# eggbothat2.net
KiCad netlist of a schematic drawn in EAGLE
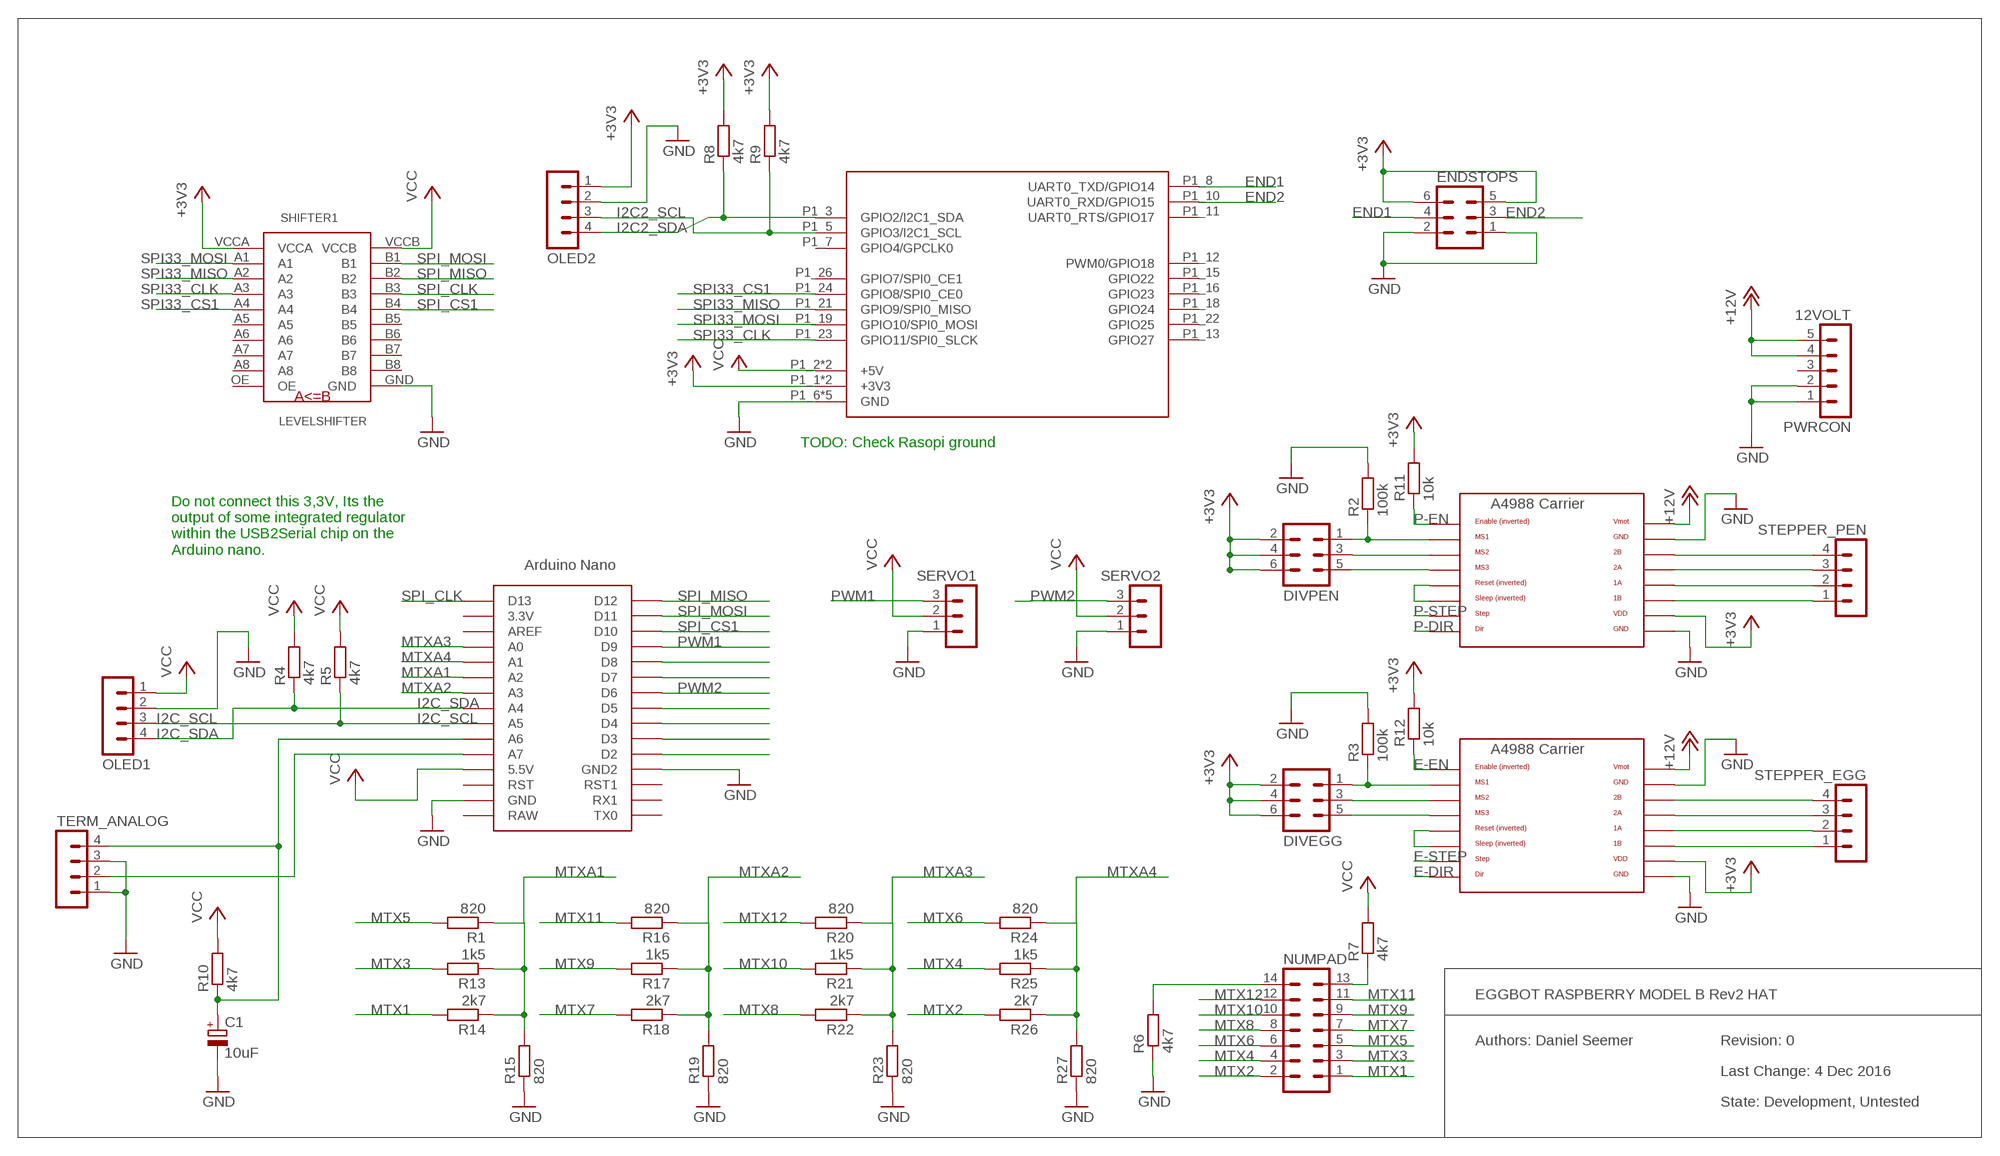
[diagram p0: schematic, sheet 1]

(export (version "E")
  (design (tool "Eeschema 10.0.6"))
  (components
    (comp (ref "12VOLT")
      (value "PWRCON")
      (footprint "eagle-import:MA05-1")
      (libsource (lib "eagle-import") (part "MA05-1"))
    )
    (comp (ref "C1")
      (value "10uF")
      (footprint "eagle-import:E2,5-5")
      (libsource (lib "eagle-import") (part "CPOL-EUE2.5-5"))
    )
    (comp (ref "DIVEGG")
      (value "MA03-2")
      (footprint "eagle-import:MA03-2")
      (libsource (lib "eagle-import") (part "MA03-2"))
    )
    (comp (ref "DIVPEN")
      (value "MA03-2")
      (footprint "eagle-import:MA03-2")
      (libsource (lib "eagle-import") (part "MA03-2"))
    )
    (comp (ref "ENDSTOPS")
      (value "MA03-2")
      (footprint "eagle-import:MA03-2")
      (libsource (lib "eagle-import") (part "MA03-2"))
    )
    (comp (ref "NUMPAD")
      (value "MA07-2")
      (footprint "eagle-import:MA07-2")
      (libsource (lib "eagle-import") (part "MA07-2"))
    )
    (comp (ref "OLED1")
      (value "MA04-1")
      (footprint "eagle-import:MA04-1")
      (libsource (lib "eagle-import") (part "MA04-1"))
    )
    (comp (ref "OLED2")
      (value "MA04-1")
      (footprint "eagle-import:MA04-1")
      (libsource (lib "eagle-import") (part "MA04-1"))
    )
    (comp (ref "R1")
      (value "820")
      (footprint "eagle-import:R1206")
      (libsource (lib "eagle-import") (part "R-EU_R1206"))
    )
    (comp (ref "R2")
      (value "100k")
      (footprint "eagle-import:R1206")
      (libsource (lib "eagle-import") (part "R-EU_R1206"))
    )
    (comp (ref "R3")
      (value "100k")
      (footprint "eagle-import:R1206")
      (libsource (lib "eagle-import") (part "R-EU_R1206"))
    )
    (comp (ref "R4")
      (value "4k7")
      (footprint "eagle-import:R1206")
      (libsource (lib "eagle-import") (part "R-EU_R1206"))
    )
    (comp (ref "R5")
      (value "4k7")
      (footprint "eagle-import:R1206")
      (libsource (lib "eagle-import") (part "R-EU_R1206"))
    )
    (comp (ref "R6")
      (value "4k7")
      (footprint "eagle-import:R1206")
      (libsource (lib "eagle-import") (part "R-EU_R1206"))
    )
    (comp (ref "R7")
      (value "4k7")
      (footprint "eagle-import:R1206")
      (libsource (lib "eagle-import") (part "R-EU_R1206"))
    )
    (comp (ref "R8")
      (value "4k7")
      (footprint "eagle-import:R1206")
      (libsource (lib "eagle-import") (part "R-EU_R1206"))
    )
    (comp (ref "R9")
      (value "4k7")
      (footprint "eagle-import:R1206")
      (libsource (lib "eagle-import") (part "R-EU_R1206"))
    )
    (comp (ref "R10")
      (value "4k7")
      (footprint "eagle-import:R1206")
      (libsource (lib "eagle-import") (part "R-EU_R1206"))
    )
    (comp (ref "R11")
      (value "10k")
      (footprint "eagle-import:R1206")
      (libsource (lib "eagle-import") (part "R-EU_R1206"))
    )
    (comp (ref "R12")
      (value "10k")
      (footprint "eagle-import:R1206")
      (libsource (lib "eagle-import") (part "R-EU_R1206"))
    )
    (comp (ref "R13")
      (value "1k5")
      (footprint "eagle-import:R1206")
      (libsource (lib "eagle-import") (part "R-EU_R1206"))
    )
    (comp (ref "R14")
      (value "2k7")
      (footprint "eagle-import:R1206")
      (libsource (lib "eagle-import") (part "R-EU_R1206"))
    )
    (comp (ref "R15")
      (value "820")
      (footprint "eagle-import:R1206")
      (libsource (lib "eagle-import") (part "R-EU_R1206"))
    )
    (comp (ref "R16")
      (value "820")
      (footprint "eagle-import:R1206")
      (libsource (lib "eagle-import") (part "R-EU_R1206"))
    )
    (comp (ref "R17")
      (value "1k5")
      (footprint "eagle-import:R1206")
      (libsource (lib "eagle-import") (part "R-EU_R1206"))
    )
    (comp (ref "R18")
      (value "2k7")
      (footprint "eagle-import:R1206")
      (libsource (lib "eagle-import") (part "R-EU_R1206"))
    )
    (comp (ref "R19")
      (value "820")
      (footprint "eagle-import:R1206")
      (libsource (lib "eagle-import") (part "R-EU_R1206"))
    )
    (comp (ref "R20")
      (value "820")
      (footprint "eagle-import:R1206")
      (libsource (lib "eagle-import") (part "R-EU_R1206"))
    )
    (comp (ref "R21")
      (value "1k5")
      (footprint "eagle-import:R1206")
      (libsource (lib "eagle-import") (part "R-EU_R1206"))
    )
    (comp (ref "R22")
      (value "2k7")
      (footprint "eagle-import:R1206")
      (libsource (lib "eagle-import") (part "R-EU_R1206"))
    )
    (comp (ref "R23")
      (value "820")
      (footprint "eagle-import:R1206")
      (libsource (lib "eagle-import") (part "R-EU_R1206"))
    )
    (comp (ref "R24")
      (value "820")
      (footprint "eagle-import:R1206")
      (libsource (lib "eagle-import") (part "R-EU_R1206"))
    )
    (comp (ref "R25")
      (value "1k5")
      (footprint "eagle-import:R1206")
      (libsource (lib "eagle-import") (part "R-EU_R1206"))
    )
    (comp (ref "R26")
      (value "2k7")
      (footprint "eagle-import:R1206")
      (libsource (lib "eagle-import") (part "R-EU_R1206"))
    )
    (comp (ref "R27")
      (value "820")
      (footprint "eagle-import:R1206")
      (libsource (lib "eagle-import") (part "R-EU_R1206"))
    )
    (comp (ref "RASPBERRY")
      (value "RPI-B-V2SHIELD")
      (footprint "eagle-import:RPI-B-V2-SHIELD")
      (libsource (lib "eagle-import") (part "RPI-B-V2SHIELD"))
    )
    (comp (ref "SERVO1")
      (value "MA03-1")
      (footprint "eagle-import:MA03-1")
      (libsource (lib "eagle-import") (part "MA03-1"))
    )
    (comp (ref "SERVO2")
      (value "MA03-1")
      (footprint "eagle-import:MA03-1")
      (libsource (lib "eagle-import") (part "MA03-1"))
    )
    (comp (ref "SHIFTER1")
      (value "LEVELSHIFTER")
      (footprint "eagle-import:PLUG_20_S4")
      (libsource (lib "eagle-import") (part "LEVELSHIFTER"))
    )
    (comp (ref "STEPPER_EGG")
      (value "MA04-1")
      (footprint "eagle-import:MA04-1")
      (libsource (lib "eagle-import") (part "MA04-1"))
    )
    (comp (ref "STEPPER_PEN")
      (value "MA04-1")
      (footprint "eagle-import:MA04-1")
      (libsource (lib "eagle-import") (part "MA04-1"))
    )
    (comp (ref "TERM_ANALOG")
      (value "MA04-1")
      (footprint "eagle-import:MA04-1")
      (libsource (lib "eagle-import") (part "MA04-1"))
    )
    (comp (ref "U$1")
      (value "A4988BREAKOUT")
      (footprint "eagle-import:A4988BREAKOUT")
      (libsource (lib "eagle-import") (part "A4988BREAKOUT"))
    )
    (comp (ref "U$2")
      (value "A4988BREAKOUT")
      (footprint "eagle-import:A4988BREAKOUT")
      (libsource (lib "eagle-import") (part "A4988BREAKOUT"))
    )
    (comp (ref "U$4")
      (value "NANO")
      (footprint "eagle-import:NANO")
      (libsource (lib "eagle-import") (part "NANO"))
    )
  )
  (nets
    (net (code "1") (name "+3V3") (class "Default")
      (node (ref "DIVEGG") (pin "2") (pinfunction "2_2") (pintype "passive"))
      (node (ref "DIVEGG") (pin "4") (pinfunction "4_4") (pintype "passive"))
      (node (ref "DIVEGG") (pin "6") (pinfunction "6_6") (pintype "passive"))
      (node (ref "DIVPEN") (pin "2") (pinfunction "2_2") (pintype "passive"))
      (node (ref "DIVPEN") (pin "4") (pinfunction "4_4") (pintype "passive"))
      (node (ref "DIVPEN") (pin "6") (pinfunction "6_6") (pintype "passive"))
      (node (ref "ENDSTOPS") (pin "5") (pinfunction "5_5") (pintype "passive"))
      (node (ref "ENDSTOPS") (pin "6") (pinfunction "6_6") (pintype "passive"))
      (node (ref "OLED2") (pin "1") (pinfunction "1_1") (pintype "passive"))
      (node (ref "R11") (pin "2") (pinfunction "2_2") (pintype "passive"))
      (node (ref "R12") (pin "2") (pinfunction "2_2") (pintype "passive"))
      (node (ref "R8") (pin "2") (pinfunction "2_2") (pintype "passive"))
      (node (ref "R9") (pin "2") (pinfunction "2_2") (pintype "passive"))
      (node (ref "RASPBERRY") (pin "P1_1") (pinfunction "+3V3_P1_1") (pintype "power_in"))
      (node (ref "RASPBERRY") (pin "P1_17") (pinfunction "+3V3_P1_17") (pintype "power_in"))
      (node (ref "SHIFTER1") (pin "VCCA") (pinfunction "VCCA_VCCA") (pintype "bidirectional"))
      (node (ref "U$1") (pin "VDD") (pinfunction "VDD_VDD") (pintype "power_in"))
      (node (ref "U$2") (pin "VDD") (pinfunction "VDD_VDD") (pintype "power_in"))
    )
    (net (code "2") (name "+12V") (class "Default")
      (node (ref "12VOLT") (pin "4") (pinfunction "4_4") (pintype "passive"))
      (node (ref "12VOLT") (pin "5") (pinfunction "5_5") (pintype "passive"))
      (node (ref "U$1") (pin "VMOT") (pinfunction "VMOT_VMOT") (pintype "power_in"))
      (node (ref "U$2") (pin "VMOT") (pinfunction "VMOT_VMOT") (pintype "power_in"))
    )
    (net (code "3") (name "E-DIR") (class "Default")
      (node (ref "U$2") (pin "DIR") (pinfunction "DIR_DIR") (pintype "input"))
    )
    (net (code "4") (name "E-EN") (class "Default")
      (node (ref "R12") (pin "1") (pinfunction "1_1") (pintype "passive"))
      (node (ref "U$2") (pin "EN") (pinfunction "EN_EN") (pintype "input"))
    )
    (net (code "5") (name "E-STEP") (class "Default")
      (node (ref "U$2") (pin "STEP") (pinfunction "STEP_STEP") (pintype "input"))
    )
    (net (code "6") (name "END1") (class "Default")
      (node (ref "ENDSTOPS") (pin "4") (pinfunction "4_4") (pintype "passive"))
      (node (ref "RASPBERRY") (pin "P1_8") (pinfunction "UART0_TXD/GPIO14_P1_8") (pintype "bidirectional"))
    )
    (net (code "7") (name "END2") (class "Default")
      (node (ref "ENDSTOPS") (pin "3") (pinfunction "3_3") (pintype "passive"))
      (node (ref "RASPBERRY") (pin "P1_10") (pinfunction "UART0_RXD/GPIO15_P1_10") (pintype "bidirectional"))
    )
    (net (code "8") (name "GND") (class "Default")
      (node (ref "12VOLT") (pin "1") (pinfunction "1_1") (pintype "passive"))
      (node (ref "12VOLT") (pin "2") (pinfunction "2_2") (pintype "passive"))
      (node (ref "C1") (pin "-") (pinfunction "-_-") (pintype "passive"))
      (node (ref "ENDSTOPS") (pin "1") (pinfunction "1_1") (pintype "passive"))
      (node (ref "ENDSTOPS") (pin "2") (pinfunction "2_2") (pintype "passive"))
      (node (ref "OLED1") (pin "2") (pinfunction "2_2") (pintype "passive"))
      (node (ref "OLED2") (pin "2") (pinfunction "2_2") (pintype "passive"))
      (node (ref "R15") (pin "1") (pinfunction "1_1") (pintype "passive"))
      (node (ref "R19") (pin "1") (pinfunction "1_1") (pintype "passive"))
      (node (ref "R2") (pin "2") (pinfunction "2_2") (pintype "passive"))
      (node (ref "R23") (pin "1") (pinfunction "1_1") (pintype "passive"))
      (node (ref "R27") (pin "1") (pinfunction "1_1") (pintype "passive"))
      (node (ref "R3") (pin "2") (pinfunction "2_2") (pintype "passive"))
      (node (ref "R6") (pin "1") (pinfunction "1_1") (pintype "passive"))
      (node (ref "RASPBERRY") (pin "P1_14") (pinfunction "GND_P1_14") (pintype "power_in"))
      (node (ref "RASPBERRY") (pin "P1_20") (pinfunction "GND_P1_20") (pintype "power_in"))
      (node (ref "RASPBERRY") (pin "P1_25") (pinfunction "GND_P1_25") (pintype "power_in"))
      (node (ref "RASPBERRY") (pin "P1_6") (pinfunction "GND_P1_6") (pintype "power_in"))
      (node (ref "RASPBERRY") (pin "P1_9") (pinfunction "GND_P1_9") (pintype "power_in"))
      (node (ref "SERVO1") (pin "1") (pinfunction "1_1") (pintype "passive"))
      (node (ref "SERVO2") (pin "1") (pinfunction "1_1") (pintype "passive"))
      (node (ref "SHIFTER1") (pin "GND") (pinfunction "GND_GND") (pintype "bidirectional"))
      (node (ref "TERM_ANALOG") (pin "1") (pinfunction "1_1") (pintype "passive"))
      (node (ref "TERM_ANALOG") (pin "3") (pinfunction "3_3") (pintype "passive"))
      (node (ref "U$1") (pin "GND") (pinfunction "GND_GND") (pintype "power_in"))
      (node (ref "U$1") (pin "GND@0") (pinfunction "GND_GND@0") (pintype "power_in"))
      (node (ref "U$2") (pin "GND") (pinfunction "GND_GND") (pintype "power_in"))
      (node (ref "U$2") (pin "GND@0") (pinfunction "GND_GND@0") (pintype "power_in"))
      (node (ref "U$4") (pin "GND") (pinfunction "GND_GND") (pintype "bidirectional"))
      (node (ref "U$4") (pin "GND1") (pinfunction "GND2_GND1") (pintype "bidirectional"))
    )
    (net (code "9") (name "I2C2_SCL") (class "Default")
      (node (ref "OLED2") (pin "3") (pinfunction "3_3") (pintype "passive"))
      (node (ref "R9") (pin "1") (pinfunction "1_1") (pintype "passive"))
      (node (ref "RASPBERRY") (pin "P1_5") (pinfunction "GPIO3/I2C1_SCL_P1_5") (pintype "bidirectional"))
    )
    (net (code "10") (name "I2C2_SDA") (class "Default")
      (node (ref "OLED2") (pin "4") (pinfunction "4_4") (pintype "passive"))
      (node (ref "R8") (pin "1") (pinfunction "1_1") (pintype "passive"))
      (node (ref "RASPBERRY") (pin "P1_3") (pinfunction "GPIO2/I2C1_SDA_P1_3") (pintype "bidirectional"))
    )
    (net (code "11") (name "I2C_SCL") (class "Default")
      (node (ref "OLED1") (pin "3") (pinfunction "3_3") (pintype "passive"))
      (node (ref "R5") (pin "1") (pinfunction "1_1") (pintype "passive"))
      (node (ref "U$4") (pin "A5") (pinfunction "A5_A5") (pintype "bidirectional"))
    )
    (net (code "12") (name "I2C_SDA") (class "Default")
      (node (ref "OLED1") (pin "4") (pinfunction "4_4") (pintype "passive"))
      (node (ref "R4") (pin "1") (pinfunction "1_1") (pintype "passive"))
      (node (ref "U$4") (pin "A4") (pinfunction "A4_A4") (pintype "bidirectional"))
    )
    (net (code "13") (name "MTX1") (class "Default")
      (node (ref "NUMPAD") (pin "1") (pinfunction "1_1") (pintype "passive"))
      (node (ref "R14") (pin "2") (pinfunction "2_2") (pintype "passive"))
    )
    (net (code "14") (name "MTX2") (class "Default")
      (node (ref "NUMPAD") (pin "2") (pinfunction "2_2") (pintype "passive"))
      (node (ref "R26") (pin "2") (pinfunction "2_2") (pintype "passive"))
    )
    (net (code "15") (name "MTX3") (class "Default")
      (node (ref "NUMPAD") (pin "3") (pinfunction "3_3") (pintype "passive"))
      (node (ref "R13") (pin "2") (pinfunction "2_2") (pintype "passive"))
    )
    (net (code "16") (name "MTX4") (class "Default")
      (node (ref "NUMPAD") (pin "4") (pinfunction "4_4") (pintype "passive"))
      (node (ref "R25") (pin "2") (pinfunction "2_2") (pintype "passive"))
    )
    (net (code "17") (name "MTX5") (class "Default")
      (node (ref "NUMPAD") (pin "5") (pinfunction "5_5") (pintype "passive"))
      (node (ref "R1") (pin "2") (pinfunction "2_2") (pintype "passive"))
    )
    (net (code "18") (name "MTX6") (class "Default")
      (node (ref "NUMPAD") (pin "6") (pinfunction "6_6") (pintype "passive"))
      (node (ref "R24") (pin "2") (pinfunction "2_2") (pintype "passive"))
    )
    (net (code "19") (name "MTX7") (class "Default")
      (node (ref "NUMPAD") (pin "7") (pinfunction "7_7") (pintype "passive"))
      (node (ref "R18") (pin "2") (pinfunction "2_2") (pintype "passive"))
    )
    (net (code "20") (name "MTX8") (class "Default")
      (node (ref "NUMPAD") (pin "8") (pinfunction "8_8") (pintype "passive"))
      (node (ref "R22") (pin "2") (pinfunction "2_2") (pintype "passive"))
    )
    (net (code "21") (name "MTX9") (class "Default")
      (node (ref "NUMPAD") (pin "9") (pinfunction "9_9") (pintype "passive"))
      (node (ref "R17") (pin "2") (pinfunction "2_2") (pintype "passive"))
    )
    (net (code "22") (name "MTX10") (class "Default")
      (node (ref "NUMPAD") (pin "10") (pinfunction "10_10") (pintype "passive"))
      (node (ref "R21") (pin "2") (pinfunction "2_2") (pintype "passive"))
    )
    (net (code "23") (name "MTX11") (class "Default")
      (node (ref "NUMPAD") (pin "11") (pinfunction "11_11") (pintype "passive"))
      (node (ref "R16") (pin "2") (pinfunction "2_2") (pintype "passive"))
    )
    (net (code "24") (name "MTX12") (class "Default")
      (node (ref "NUMPAD") (pin "12") (pinfunction "12_12") (pintype "passive"))
      (node (ref "R20") (pin "2") (pinfunction "2_2") (pintype "passive"))
    )
    (net (code "25") (name "MTXA1") (class "Default")
      (node (ref "R1") (pin "1") (pinfunction "1_1") (pintype "passive"))
      (node (ref "R13") (pin "1") (pinfunction "1_1") (pintype "passive"))
      (node (ref "R14") (pin "1") (pinfunction "1_1") (pintype "passive"))
      (node (ref "R15") (pin "2") (pinfunction "2_2") (pintype "passive"))
      (node (ref "U$4") (pin "A2") (pinfunction "A2_A2") (pintype "bidirectional"))
    )
    (net (code "26") (name "MTXA2") (class "Default")
      (node (ref "R16") (pin "1") (pinfunction "1_1") (pintype "passive"))
      (node (ref "R17") (pin "1") (pinfunction "1_1") (pintype "passive"))
      (node (ref "R18") (pin "1") (pinfunction "1_1") (pintype "passive"))
      (node (ref "R19") (pin "2") (pinfunction "2_2") (pintype "passive"))
      (node (ref "U$4") (pin "A3") (pinfunction "A3_A3") (pintype "bidirectional"))
    )
    (net (code "27") (name "MTXA3") (class "Default")
      (node (ref "R20") (pin "1") (pinfunction "1_1") (pintype "passive"))
      (node (ref "R21") (pin "1") (pinfunction "1_1") (pintype "passive"))
      (node (ref "R22") (pin "1") (pinfunction "1_1") (pintype "passive"))
      (node (ref "R23") (pin "2") (pinfunction "2_2") (pintype "passive"))
      (node (ref "U$4") (pin "A0") (pinfunction "A0_A0") (pintype "bidirectional"))
    )
    (net (code "28") (name "MTXA4") (class "Default")
      (node (ref "R24") (pin "1") (pinfunction "1_1") (pintype "passive"))
      (node (ref "R25") (pin "1") (pinfunction "1_1") (pintype "passive"))
      (node (ref "R26") (pin "1") (pinfunction "1_1") (pintype "passive"))
      (node (ref "R27") (pin "2") (pinfunction "2_2") (pintype "passive"))
      (node (ref "U$4") (pin "A1") (pinfunction "A1_A1") (pintype "bidirectional"))
    )
    (net (code "29") (name "Net-(C1-Pad+)") (class "Default")
      (node (ref "C1") (pin "+") (pinfunction "+_+") (pintype "passive"))
      (node (ref "R10") (pin "1") (pinfunction "1_1") (pintype "passive"))
      (node (ref "TERM_ANALOG") (pin "4") (pinfunction "4_4") (pintype "passive"))
      (node (ref "U$4") (pin "A6") (pinfunction "A6_A6") (pintype "bidirectional"))
    )
    (net (code "30") (name "Net-(DIVEGG-Pad1)") (class "Default")
      (node (ref "DIVEGG") (pin "1") (pinfunction "1_1") (pintype "passive"))
      (node (ref "R3") (pin "1") (pinfunction "1_1") (pintype "passive"))
      (node (ref "U$2") (pin "MS1") (pinfunction "MS1_MS1") (pintype "input"))
    )
    (net (code "31") (name "Net-(DIVEGG-Pad3)") (class "Default")
      (node (ref "DIVEGG") (pin "3") (pinfunction "3_3") (pintype "passive"))
      (node (ref "U$2") (pin "MS2") (pinfunction "MS2_MS2") (pintype "input"))
    )
    (net (code "32") (name "Net-(DIVEGG-Pad5)") (class "Default")
      (node (ref "DIVEGG") (pin "5") (pinfunction "5_5") (pintype "passive"))
      (node (ref "U$2") (pin "MS3") (pinfunction "MS3_MS3") (pintype "input"))
    )
    (net (code "33") (name "Net-(DIVPEN-Pad1)") (class "Default")
      (node (ref "DIVPEN") (pin "1") (pinfunction "1_1") (pintype "passive"))
      (node (ref "R2") (pin "1") (pinfunction "1_1") (pintype "passive"))
      (node (ref "U$1") (pin "MS1") (pinfunction "MS1_MS1") (pintype "input"))
    )
    (net (code "34") (name "Net-(DIVPEN-Pad3)") (class "Default")
      (node (ref "DIVPEN") (pin "3") (pinfunction "3_3") (pintype "passive"))
      (node (ref "U$1") (pin "MS2") (pinfunction "MS2_MS2") (pintype "input"))
    )
    (net (code "35") (name "Net-(DIVPEN-Pad5)") (class "Default")
      (node (ref "DIVPEN") (pin "5") (pinfunction "5_5") (pintype "passive"))
      (node (ref "U$1") (pin "MS3") (pinfunction "MS3_MS3") (pintype "input"))
    )
    (net (code "36") (name "Net-(NUMPAD-Pad13)") (class "Default")
      (node (ref "NUMPAD") (pin "13") (pinfunction "13_13") (pintype "passive"))
      (node (ref "R7") (pin "1") (pinfunction "1_1") (pintype "passive"))
    )
    (net (code "37") (name "Net-(NUMPAD-Pad14)") (class "Default")
      (node (ref "NUMPAD") (pin "14") (pinfunction "14_14") (pintype "passive"))
      (node (ref "R6") (pin "2") (pinfunction "2_2") (pintype "passive"))
    )
    (net (code "38") (name "Net-(STEPPER_EGG-Pad1)") (class "Default")
      (node (ref "STEPPER_EGG") (pin "1") (pinfunction "1_1") (pintype "passive"))
      (node (ref "U$2") (pin "1B") (pinfunction "1B_1B") (pintype "output"))
    )
    (net (code "39") (name "Net-(STEPPER_EGG-Pad2)") (class "Default")
      (node (ref "STEPPER_EGG") (pin "2") (pinfunction "2_2") (pintype "passive"))
      (node (ref "U$2") (pin "1A") (pinfunction "1A_1A") (pintype "output"))
    )
    (net (code "40") (name "Net-(STEPPER_EGG-Pad3)") (class "Default")
      (node (ref "STEPPER_EGG") (pin "3") (pinfunction "3_3") (pintype "passive"))
      (node (ref "U$2") (pin "2A") (pinfunction "2A_2A") (pintype "output"))
    )
    (net (code "41") (name "Net-(STEPPER_EGG-Pad4)") (class "Default")
      (node (ref "STEPPER_EGG") (pin "4") (pinfunction "4_4") (pintype "passive"))
      (node (ref "U$2") (pin "2B") (pinfunction "2B_2B") (pintype "output"))
    )
    (net (code "42") (name "Net-(STEPPER_PEN-Pad1)") (class "Default")
      (node (ref "STEPPER_PEN") (pin "1") (pinfunction "1_1") (pintype "passive"))
      (node (ref "U$1") (pin "1B") (pinfunction "1B_1B") (pintype "output"))
    )
    (net (code "43") (name "Net-(STEPPER_PEN-Pad2)") (class "Default")
      (node (ref "STEPPER_PEN") (pin "2") (pinfunction "2_2") (pintype "passive"))
      (node (ref "U$1") (pin "1A") (pinfunction "1A_1A") (pintype "output"))
    )
    (net (code "44") (name "Net-(STEPPER_PEN-Pad3)") (class "Default")
      (node (ref "STEPPER_PEN") (pin "3") (pinfunction "3_3") (pintype "passive"))
      (node (ref "U$1") (pin "2A") (pinfunction "2A_2A") (pintype "output"))
    )
    (net (code "45") (name "Net-(STEPPER_PEN-Pad4)") (class "Default")
      (node (ref "STEPPER_PEN") (pin "4") (pinfunction "4_4") (pintype "passive"))
      (node (ref "U$1") (pin "2B") (pinfunction "2B_2B") (pintype "output"))
    )
    (net (code "46") (name "Net-(TERM_ANALOG-Pad2)") (class "Default")
      (node (ref "TERM_ANALOG") (pin "2") (pinfunction "2_2") (pintype "passive"))
      (node (ref "U$4") (pin "A7") (pinfunction "A7_A7") (pintype "bidirectional"))
    )
    (net (code "47") (name "Net-(U$1-SLEEP)") (class "Default")
      (node (ref "U$1") (pin "RST") (pinfunction "RST_RST") (pintype "input"))
      (node (ref "U$1") (pin "SLP") (pinfunction "SLEEP_SLP") (pintype "input"))
    )
    (net (code "48") (name "Net-(U$2-SLEEP)") (class "Default")
      (node (ref "U$2") (pin "RST") (pinfunction "RST_RST") (pintype "input"))
      (node (ref "U$2") (pin "SLP") (pinfunction "SLEEP_SLP") (pintype "input"))
    )
    (net (code "49") (name "P-DIR") (class "Default")
      (node (ref "U$1") (pin "DIR") (pinfunction "DIR_DIR") (pintype "input"))
    )
    (net (code "50") (name "P-EN") (class "Default")
      (node (ref "R11") (pin "1") (pinfunction "1_1") (pintype "passive"))
      (node (ref "U$1") (pin "EN") (pinfunction "EN_EN") (pintype "input"))
    )
    (net (code "51") (name "P-STEP") (class "Default")
      (node (ref "U$1") (pin "STEP") (pinfunction "STEP_STEP") (pintype "input"))
    )
    (net (code "52") (name "PWM1") (class "Default")
      (node (ref "SERVO1") (pin "3") (pinfunction "3_3") (pintype "passive"))
      (node (ref "U$4") (pin "D9") (pinfunction "D9_D9") (pintype "bidirectional"))
    )
    (net (code "53") (name "PWM2") (class "Default")
      (node (ref "SERVO2") (pin "3") (pinfunction "3_3") (pintype "passive"))
      (node (ref "U$4") (pin "D6") (pinfunction "D6_D6") (pintype "bidirectional"))
    )
    (net (code "54") (name "SPI33_CLK") (class "Default")
      (node (ref "RASPBERRY") (pin "P1_23") (pinfunction "GPIO11/SPI0_SLCK_P1_23") (pintype "bidirectional"))
      (node (ref "SHIFTER1") (pin "A3") (pinfunction "A3_A3") (pintype "bidirectional"))
    )
    (net (code "55") (name "SPI33_CS1") (class "Default")
      (node (ref "RASPBERRY") (pin "P1_24") (pinfunction "GPIO8/SPI0_CE0_P1_24") (pintype "bidirectional"))
      (node (ref "SHIFTER1") (pin "A4") (pinfunction "A4_A4") (pintype "bidirectional"))
    )
    (net (code "56") (name "SPI33_MISO") (class "Default")
      (node (ref "RASPBERRY") (pin "P1_21") (pinfunction "GPIO9/SPI0_MISO_P1_21") (pintype "bidirectional"))
      (node (ref "SHIFTER1") (pin "A2") (pinfunction "A2_A2") (pintype "bidirectional"))
    )
    (net (code "57") (name "SPI33_MOSI") (class "Default")
      (node (ref "RASPBERRY") (pin "P1_19") (pinfunction "GPIO10/SPI0_MOSI_P1_19") (pintype "bidirectional"))
      (node (ref "SHIFTER1") (pin "A1") (pinfunction "A1_A1") (pintype "bidirectional"))
    )
    (net (code "58") (name "SPI_CLK") (class "Default")
      (node (ref "SHIFTER1") (pin "B3") (pinfunction "B3_B3") (pintype "bidirectional"))
      (node (ref "U$4") (pin "D13") (pinfunction "D13_D13") (pintype "bidirectional"))
    )
    (net (code "59") (name "SPI_CS1") (class "Default")
      (node (ref "SHIFTER1") (pin "B4") (pinfunction "B4_B4") (pintype "bidirectional"))
      (node (ref "U$4") (pin "D10") (pinfunction "D10_D10") (pintype "bidirectional"))
    )
    (net (code "60") (name "SPI_MISO") (class "Default")
      (node (ref "SHIFTER1") (pin "B2") (pinfunction "B2_B2") (pintype "bidirectional"))
      (node (ref "U$4") (pin "D12") (pinfunction "D12_D12") (pintype "bidirectional"))
    )
    (net (code "61") (name "SPI_MOSI") (class "Default")
      (node (ref "SHIFTER1") (pin "B1") (pinfunction "B1_B1") (pintype "bidirectional"))
      (node (ref "U$4") (pin "D11") (pinfunction "D11_D11") (pintype "bidirectional"))
    )
    (net (code "62") (name "VCC") (class "Default")
      (node (ref "OLED1") (pin "1") (pinfunction "1_1") (pintype "passive"))
      (node (ref "R10") (pin "2") (pinfunction "2_2") (pintype "passive"))
      (node (ref "R4") (pin "2") (pinfunction "2_2") (pintype "passive"))
      (node (ref "R5") (pin "2") (pinfunction "2_2") (pintype "passive"))
      (node (ref "R7") (pin "2") (pinfunction "2_2") (pintype "passive"))
      (node (ref "RASPBERRY") (pin "P1_2") (pinfunction "+5V_P1_2") (pintype "power_in"))
      (node (ref "RASPBERRY") (pin "P1_4") (pinfunction "+5V_P1_4") (pintype "power_in"))
      (node (ref "SERVO1") (pin "2") (pinfunction "2_2") (pintype "passive"))
      (node (ref "SERVO2") (pin "2") (pinfunction "2_2") (pintype "passive"))
      (node (ref "SHIFTER1") (pin "VCCB") (pinfunction "VCCB_VCCB") (pintype "bidirectional"))
      (node (ref "U$4") (pin "5V") (pinfunction "5.5V_5V") (pintype "bidirectional"))
    )
    (net (code "63") (name "unconnected-(12VOLT-Pad3)") (class "Default")
      (node (ref "12VOLT") (pin "3") (pinfunction "3_3") (pintype "passive"))
    )
    (net (code "64") (name "unconnected-(RASPBERRY-GPIO4{slash}GPCLK0-PadP1_7)") (class "Default")
      (node (ref "RASPBERRY") (pin "P1_7") (pinfunction "GPIO4/GPCLK0_P1_7") (pintype "bidirectional"))
    )
    (net (code "65") (name "unconnected-(RASPBERRY-GPIO7{slash}SPI0_CE1-PadP1_26)") (class "Default")
      (node (ref "RASPBERRY") (pin "P1_26") (pinfunction "GPIO7/SPI0_CE1_P1_26") (pintype "bidirectional"))
    )
    (net (code "66") (name "unconnected-(RASPBERRY-GPIO22-PadP1_15)") (class "Default")
      (node (ref "RASPBERRY") (pin "P1_15") (pinfunction "GPIO22_P1_15") (pintype "bidirectional"))
    )
    (net (code "67") (name "unconnected-(RASPBERRY-GPIO23-PadP1_16)") (class "Default")
      (node (ref "RASPBERRY") (pin "P1_16") (pinfunction "GPIO23_P1_16") (pintype "bidirectional"))
    )
    (net (code "68") (name "unconnected-(RASPBERRY-GPIO24-PadP1_18)") (class "Default")
      (node (ref "RASPBERRY") (pin "P1_18") (pinfunction "GPIO24_P1_18") (pintype "bidirectional"))
    )
    (net (code "69") (name "unconnected-(RASPBERRY-GPIO25-PadP1_22)") (class "Default")
      (node (ref "RASPBERRY") (pin "P1_22") (pinfunction "GPIO25_P1_22") (pintype "bidirectional"))
    )
    (net (code "70") (name "unconnected-(RASPBERRY-GPIO27-PadP1_13)") (class "Default")
      (node (ref "RASPBERRY") (pin "P1_13") (pinfunction "GPIO27_P1_13") (pintype "bidirectional"))
    )
    (net (code "71") (name "unconnected-(RASPBERRY-PWM0{slash}GPIO18-PadP1_12)") (class "Default")
      (node (ref "RASPBERRY") (pin "P1_12") (pinfunction "PWM0/GPIO18_P1_12") (pintype "bidirectional"))
    )
    (net (code "72") (name "unconnected-(RASPBERRY-UART0_RTS{slash}GPIO17-PadP1_11)") (class "Default")
      (node (ref "RASPBERRY") (pin "P1_11") (pinfunction "UART0_RTS/GPIO17_P1_11") (pintype "bidirectional"))
    )
    (net (code "73") (name "unconnected-(SHIFTER1-PadA5)") (class "Default")
      (node (ref "SHIFTER1") (pin "A5") (pinfunction "A5_A5") (pintype "bidirectional"))
    )
    (net (code "74") (name "unconnected-(SHIFTER1-PadA6)") (class "Default")
      (node (ref "SHIFTER1") (pin "A6") (pinfunction "A6_A6") (pintype "bidirectional"))
    )
    (net (code "75") (name "unconnected-(SHIFTER1-PadA7)") (class "Default")
      (node (ref "SHIFTER1") (pin "A7") (pinfunction "A7_A7") (pintype "bidirectional"))
    )
    (net (code "76") (name "unconnected-(SHIFTER1-PadA8)") (class "Default")
      (node (ref "SHIFTER1") (pin "A8") (pinfunction "A8_A8") (pintype "bidirectional"))
    )
    (net (code "77") (name "unconnected-(SHIFTER1-PadB5)") (class "Default")
      (node (ref "SHIFTER1") (pin "B5") (pinfunction "B5_B5") (pintype "bidirectional"))
    )
    (net (code "78") (name "unconnected-(SHIFTER1-PadB6)") (class "Default")
      (node (ref "SHIFTER1") (pin "B6") (pinfunction "B6_B6") (pintype "bidirectional"))
    )
    (net (code "79") (name "unconnected-(SHIFTER1-PadB7)") (class "Default")
      (node (ref "SHIFTER1") (pin "B7") (pinfunction "B7_B7") (pintype "bidirectional"))
    )
    (net (code "80") (name "unconnected-(SHIFTER1-PadB8)") (class "Default")
      (node (ref "SHIFTER1") (pin "B8") (pinfunction "B8_B8") (pintype "bidirectional"))
    )
    (net (code "81") (name "unconnected-(SHIFTER1-PadOE)") (class "Default")
      (node (ref "SHIFTER1") (pin "OE") (pinfunction "OE_OE") (pintype "bidirectional"))
    )
    (net (code "82") (name "unconnected-(U$4-Pad3.3V)") (class "Default")
      (node (ref "U$4") (pin "3.3V") (pinfunction "3.3V_3.3V") (pintype "bidirectional"))
    )
    (net (code "83") (name "unconnected-(U$4-PadAREF)") (class "Default")
      (node (ref "U$4") (pin "AREF") (pinfunction "AREF_AREF") (pintype "bidirectional"))
    )
    (net (code "84") (name "unconnected-(U$4-PadD2)") (class "Default")
      (node (ref "U$4") (pin "D2") (pinfunction "D2_D2") (pintype "bidirectional"))
    )
    (net (code "85") (name "unconnected-(U$4-PadD3)") (class "Default")
      (node (ref "U$4") (pin "D3") (pinfunction "D3_D3") (pintype "bidirectional"))
    )
    (net (code "86") (name "unconnected-(U$4-PadD4)") (class "Default")
      (node (ref "U$4") (pin "D4") (pinfunction "D4_D4") (pintype "bidirectional"))
    )
    (net (code "87") (name "unconnected-(U$4-PadD5)") (class "Default")
      (node (ref "U$4") (pin "D5") (pinfunction "D5_D5") (pintype "bidirectional"))
    )
    (net (code "88") (name "unconnected-(U$4-PadD7)") (class "Default")
      (node (ref "U$4") (pin "D7") (pinfunction "D7_D7") (pintype "bidirectional"))
    )
    (net (code "89") (name "unconnected-(U$4-PadD8)") (class "Default")
      (node (ref "U$4") (pin "D8") (pinfunction "D8_D8") (pintype "bidirectional"))
    )
    (net (code "90") (name "unconnected-(U$4-PadRAW)") (class "Default")
      (node (ref "U$4") (pin "RAW") (pinfunction "RAW_RAW") (pintype "bidirectional"))
    )
    (net (code "91") (name "unconnected-(U$4-PadRST)") (class "Default")
      (node (ref "U$4") (pin "RST") (pinfunction "RST_RST") (pintype "bidirectional"))
    )
    (net (code "92") (name "unconnected-(U$4-PadRST1)") (class "Default")
      (node (ref "U$4") (pin "RST1") (pinfunction "RST1_RST1") (pintype "bidirectional"))
    )
    (net (code "93") (name "unconnected-(U$4-PadRX1)") (class "Default")
      (node (ref "U$4") (pin "RX1") (pinfunction "RX1_RX1") (pintype "bidirectional"))
    )
    (net (code "94") (name "unconnected-(U$4-PadTX0)") (class "Default")
      (node (ref "U$4") (pin "TX0") (pinfunction "TX0_TX0") (pintype "bidirectional"))
    )
  )
)
